# soldering.net
KiCad netlist of a schematic drawn in Altium Designer
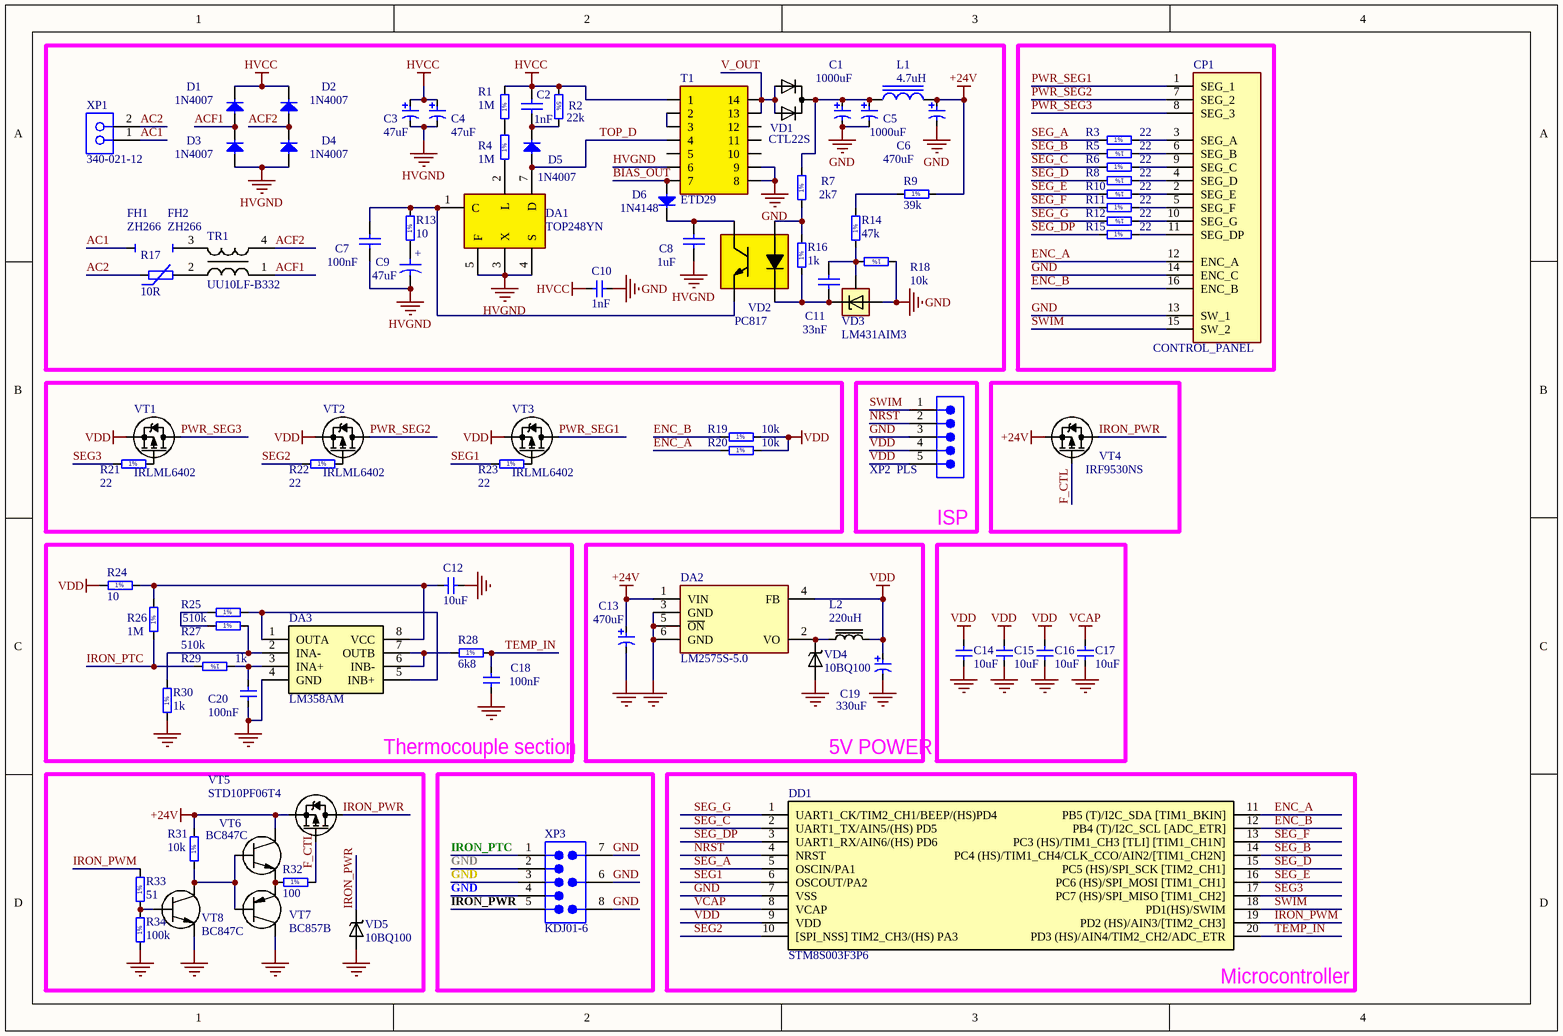
[diagram p0: soldering.SchDoc]

(export (version "E")
  (design (tool "Eeschema 10.0.6"))
  (components
    (comp (ref "C1")
      (value "1000uF")
      (footprint "CAP_EL_13_20_VERT")
      (fields (field (name "PART NUMBER") "SK035M1000B5S-1320 (VERT MOUNTED)") (field (name "VOLTAGE") "35V"))
      (libsource (lib "Capacitor") (part "CAP_POLAR"))
    )
    (comp (ref "C2")
      (value "1nF")
      (footprint "CAPR500-250X720X650")
      (description "Non-polarised capacitor")
      (fields
        (field (name "PART NUMBER") "CPER_1NF_63V_10%_500-250X720X650")
        (field (name "VOLTAGE") "63VDC/40VAC")
        (field (name "AUTHOR") "CERN DEM JLC")
      )
      (libsource (lib "Capacitors") (part "Capacitor - non polarized"))
    )
    (comp (ref "C3")
      (value "47uF")
      (footprint "CAP_EL_16_25_LEFT")
      (fields
        (field (name "PART NUMBER") "SH400M0047B7F-1625 (LEFT MOUNTED)")
        (field (name "VOLTAGE") "400V")
      )
      (libsource (lib "Capacitor") (part "CAP_POLAR"))
    )
    (comp (ref "C4")
      (value "47uF")
      (footprint "CAP_EL_16_25_LEFT")
      (fields
        (field (name "PART NUMBER") "SH400M0047B7F-1625 (LEFT MOUNTED)")
        (field (name "VOLTAGE") "400V")
      )
      (libsource (lib "Capacitor") (part "CAP_POLAR"))
    )
    (comp (ref "C5")
      (value "1000uF")
      (footprint "CAP_EL_13_20_VERT")
      (fields (field (name "PART NUMBER") "SK035M1000B5S-1320 (VERT MOUNTED)") (field (name "VOLTAGE") "35V"))
      (libsource (lib "Capacitor") (part "CAP_POLAR"))
    )
    (comp (ref "C6")
      (value "470uF")
      (footprint "CAP_EL_10_19_VERT")
      (fields (field (name "PART NUMBER") "SJ035M0470B5S-1019 (VERT MOUNTED)") (field (name "VOLTAGE") "35V"))
      (libsource (lib "Capacitor") (part "CAP_POLAR"))
    )
    (comp (ref "C7")
      (value "100nF")
      (footprint "CAPRR508-350X500X500")
      (description "Non-polarised capacitor")
      (fields
        (field (name "PART NUMBER") "CCR_100NF_50V_10%_X7R_508-350X500X500")
        (field (name "VOLTAGE") "50VDC")
        (field (name "AUTHOR") "CERN DEM JLC")
      )
      (libsource (lib "Capacitors") (part "Capacitor - non polarized"))
    )
    (comp (ref "C8")
      (value "1uF")
      (footprint "CAPRR508-508X762X914")
      (description "Non-polarised capacitor")
      (fields
        (field (name "PART NUMBER") "CCR_1UF_50V_10%_X7R_508-508X762X914")
        (field (name "VOLTAGE") "50VDC")
        (field (name "AUTHOR") "CERN DEM JLC")
      )
      (libsource (lib "Capacitors") (part "Capacitor - non polarized"))
    )
    (comp (ref "C9")
      (value "47uF")
      (footprint "CAPPR350-800X1150")
      (description "Polarised capacitor")
      (fields
        (field (name "PART NUMBER") "CAER_47UF_63V_20%_350-800X1150")
        (field (name "VOLTAGE") "63V")
        (field (name "AUTHOR") "CERN DEM JLC")
      )
      (libsource (lib "Capacitors") (part "Capacitor - polarized"))
    )
    (comp (ref "C10")
      (value "1nF")
      (footprint "CAP_7MM_Y")
      (description "SMD 0805 Capacitor")
      (fields (field (name "PART NUMBER") "VKO102KCQTC0KR") (field (name "VOLTAGE") "1000V"))
      (libsource (lib "Capacitor") (part "CAP_NON_POLAR"))
    )
    (comp (ref "C11")
      (value "33nF")
      (footprint "CAPRR254-318X508X660")
      (description "Non-polarised capacitor")
      (fields
        (field (name "PART NUMBER") "CCR_33NF_100V_10%_X7R_254-318X508X660")
        (field (name "VOLTAGE") "100VDC")
        (field (name "AUTHOR") "CERN DEM JLC")
      )
      (libsource (lib "Capacitors") (part "Capacitor - non polarized"))
    )
    (comp (ref "C12")
      (value "10uF")
      (footprint "CAP0805R")
      (description "SMD 0805 Capacitor")
      (fields
        (field (name "PART NUMBER") "CC0805_10UF_10V_10%_X7R")
        (field (name "VOLTAGE") "10V")
        (field (name "AUTHOR") "I. Kuznetsov")
      )
      (libsource (lib "Capacitor") (part "CAP_NON_POLAR"))
    )
    (comp (ref "C13")
      (value "470uF")
      (footprint "CAP_EL_10_19_VERT")
      (fields (field (name "PART NUMBER") "SH050M0470B5S-1019 (VERT MOUNTED)") (field (name "VOLTAGE") "50V"))
      (libsource (lib "Capacitor") (part "CAP_POLAR"))
    )
    (comp (ref "C14")
      (value "10uF")
      (footprint "CAP0805R")
      (description "SMD 0805 Capacitor")
      (fields
        (field (name "PART NUMBER") "CC0805_10UF_10V_10%_X7R")
        (field (name "VOLTAGE") "10V")
        (field (name "AUTHOR") "I. Kuznetsov")
      )
      (libsource (lib "Capacitor") (part "CAP_NON_POLAR"))
    )
    (comp (ref "C15")
      (value "10uF")
      (footprint "CAP0805R")
      (description "SMD 0805 Capacitor")
      (fields
        (field (name "PART NUMBER") "CC0805_10UF_10V_10%_X7R")
        (field (name "VOLTAGE") "10V")
        (field (name "AUTHOR") "I. Kuznetsov")
      )
      (libsource (lib "Capacitor") (part "CAP_NON_POLAR"))
    )
    (comp (ref "C16")
      (value "10uF")
      (footprint "CAP0805R")
      (description "SMD 0805 Capacitor")
      (fields
        (field (name "PART NUMBER") "CC0805_10UF_10V_10%_X7R")
        (field (name "VOLTAGE") "10V")
        (field (name "AUTHOR") "I. Kuznetsov")
      )
      (libsource (lib "Capacitor") (part "CAP_NON_POLAR"))
    )
    (comp (ref "C17")
      (value "10uF")
      (footprint "CAP0805R")
      (description "SMD 0805 Capacitor")
      (fields
        (field (name "PART NUMBER") "CC0805_10UF_10V_10%_X7R")
        (field (name "VOLTAGE") "10V")
        (field (name "AUTHOR") "I. Kuznetsov")
      )
      (libsource (lib "Capacitor") (part "CAP_NON_POLAR"))
    )
    (comp (ref "C18")
      (value "100nF")
      (footprint "CAP0805R")
      (description "SMD 0805 Capacitor")
      (fields
        (field (name "PART NUMBER") "CC0805_100NF_50V_10%_X7R")
        (field (name "VOLTAGE") "50V")
        (field (name "AUTHOR") "I. Kuznetsov")
      )
      (libsource (lib "Capacitor") (part "CAP_NON_POLAR"))
    )
    (comp (ref "C19")
      (value "330uF")
      (footprint "TAN_D")
      (fields (field (name "PART NUMBER") "T495D337M010AHE100") (field (name "VOLTAGE") "10V"))
      (libsource (lib "Capacitor") (part "CAP_POLAR"))
    )
    (comp (ref "C20")
      (value "100nF")
      (footprint "CAP0805R")
      (description "SMD 0805 Capacitor")
      (fields
        (field (name "PART NUMBER") "CC0805_100NF_50V_10%_X7R")
        (field (name "VOLTAGE") "50V")
        (field (name "AUTHOR") "I. Kuznetsov")
      )
      (libsource (lib "Capacitor") (part "CAP_NON_POLAR"))
    )
    (comp (ref "CP1")
      (value "CONTROL_PANEL")
      (footprint "CONTROL_PANEL")
      (libsource (lib "soldering") (part "CONTROL_PANEL"))
    )
    (comp (ref "D1")
      (value "1N4007")
      (footprint "DO-41")
      (description "Diode")
      (fields
        (field (name "VOLTAGE") "1000V")
        (field (name "POWER") "1A")
        (field (name "AUTHOR") "CERN DEM JLC")
      )
      (libsource (lib "ICs And Semiconductors") (part "Diode"))
    )
    (comp (ref "D2")
      (value "1N4007")
      (footprint "DO-41")
      (description "Diode")
      (fields
        (field (name "VOLTAGE") "1000V")
        (field (name "POWER") "1A")
        (field (name "AUTHOR") "CERN DEM JLC")
      )
      (libsource (lib "ICs And Semiconductors") (part "Diode"))
    )
    (comp (ref "D3")
      (value "1N4007")
      (footprint "DO-41")
      (description "Diode")
      (fields
        (field (name "VOLTAGE") "1000V")
        (field (name "POWER") "1A")
        (field (name "AUTHOR") "CERN DEM JLC")
      )
      (libsource (lib "ICs And Semiconductors") (part "Diode"))
    )
    (comp (ref "D4")
      (value "1N4007")
      (footprint "DO-41")
      (description "Diode")
      (fields
        (field (name "VOLTAGE") "1000V")
        (field (name "POWER") "1A")
        (field (name "AUTHOR") "CERN DEM JLC")
      )
      (libsource (lib "ICs And Semiconductors") (part "Diode"))
    )
    (comp (ref "D5")
      (value "1N4007")
      (footprint "DO-41")
      (description "Diode")
      (fields
        (field (name "VOLTAGE") "1000V")
        (field (name "POWER") "1A")
        (field (name "AUTHOR") "CERN DEM JLC")
      )
      (libsource (lib "ICs And Semiconductors") (part "Diode"))
    )
    (comp (ref "D6")
      (value "1N4148")
      (footprint "DO-35")
      (description "Diode")
      (fields
        (field (name "VOLTAGE") "100V")
        (field (name "POWER") "200mA")
        (field (name "AUTHOR") "CERN DEM JLC")
      )
      (libsource (lib "ICs And Semiconductors") (part "Diode"))
    )
    (comp (ref "DA1")
      (value "TOP248YN")
      (footprint "TO-220-7")
      (libsource (lib "IC And Semiconductor") (part "TOP24x"))
    )
    (comp (ref "DA2")
      (value "LM2575S-5.0")
      (footprint "TO-263-5")
      (fields (field (name "MANUFACTURER") "TI") (field (name "AUTHOR") "I. Kuznetsov"))
      (libsource (lib "IC And Semiconductor") (part "LM2575S"))
    )
    (comp (ref "DA3")
      (value "OP Amp")
      (footprint "SOP8")
      (fields (field (name "PARTNUMBER") "LM358AM"))
      (libsource (lib "tonometr") (part "LM358AM"))
    )
    (comp (ref "DD1")
      (value "8 Bit MCU")
      (footprint "TSSOP20")
      (description "8 Bit MCU (STmicroelectronics)")
      (fields (field (name "PARTNUMBER") "STM8S003F3P6"))
      (libsource (lib "soldering") (part "STM8S003F3P6"))
    )
    (comp (ref "FH1") (value "ZH266") (footprint "ZH266") (libsource (lib "Connector") (part "Fuse Clip")))
    (comp (ref "FH2") (value "ZH266") (footprint "ZH266") (libsource (lib "Connector") (part "Fuse Clip")))
    (comp (ref "L1")
      (value "4.7uH")
      (footprint "SL1016")
      (fields (field (name "PART NUMBER") "SL1016-4R7K 4.7"))
      (libsource (lib "Transformer") (part "CORE_IND"))
    )
    (comp (ref "L2")
      (value "220uH")
      (footprint "SDR1005")
      (fields (field (name "PART NUMBER") "SDR1005-221KL"))
      (libsource (lib "Transformer") (part "Core_Inductor"))
    )
    (comp (ref "R1")
      (value "1M")
      (footprint "RES_AXIAL_0_25_8")
      (fields
        (field (name "PART NUMBER") "RMF_1M_1%_0.6W_50PPM_1016-630X250")
        (field (name "POWER") "0.6W")
        (field (name "TOLERANCE") "±1%")
        (field (name "AUTHOR") "CERN DEM JLC")
      )
      (libsource (lib "Resistor") (part "Resistor - 1%"))
    )
    (comp (ref "R2")
      (value "22k")
      (footprint "RESADV508-1670X520")
      (description "Resistor - 5%")
      (fields
        (field (name "PART NUMBER") "RMF_22K_5%_3W_250PPM_508-1670X520_v")
        (field (name "POWER") "3W")
        (field (name "AUTHOR") "CERN DEM JLC")
      )
      (libsource (lib "Resistors") (part "Resistor - 5%"))
    )
    (comp (ref "R3")
      (value "22")
      (footprint "RES0805R")
      (fields
        (field (name "PART NUMBER") "R0805_22R_1%_0.125W_100PPM")
        (field (name "POWER") "0.125W")
        (field (name "TOLERANCE") "±1%")
        (field (name "AUTHOR") "CERN DEM JLC")
      )
      (libsource (lib "Resistor") (part "Resistor - 1%"))
    )
    (comp (ref "R4")
      (value "1M")
      (footprint "RES_AXIAL_0_25_8")
      (fields
        (field (name "PART NUMBER") "RMF_1M_1%_0.6W_50PPM_1016-630X250")
        (field (name "POWER") "0.6W")
        (field (name "TOLERANCE") "±1%")
        (field (name "AUTHOR") "CERN DEM JLC")
      )
      (libsource (lib "Resistor") (part "Resistor - 1%"))
    )
    (comp (ref "R5")
      (value "22")
      (footprint "RES0805R")
      (fields
        (field (name "PART NUMBER") "R0805_22R_1%_0.125W_100PPM")
        (field (name "POWER") "0.125W")
        (field (name "TOLERANCE") "±1%")
        (field (name "AUTHOR") "CERN DEM JLC")
      )
      (libsource (lib "Resistor") (part "Resistor - 1%"))
    )
    (comp (ref "R6")
      (value "22")
      (footprint "RES0805R")
      (fields
        (field (name "PART NUMBER") "R0805_22R_1%_0.125W_100PPM")
        (field (name "POWER") "0.125W")
        (field (name "TOLERANCE") "±1%")
        (field (name "AUTHOR") "CERN DEM JLC")
      )
      (libsource (lib "Resistor") (part "Resistor - 1%"))
    )
    (comp (ref "R7")
      (value "2k7")
      (footprint "RES1016-630X250")
      (description "Resistor - 1%")
      (fields
        (field (name "PART NUMBER") "RMF_2K7_1%_0.6W_50PPM_1016-630X250")
        (field (name "POWER") "0.6W")
        (field (name "AUTHOR") "CERN DEM JLC")
      )
      (libsource (lib "Resistors") (part "Resistor - 1%"))
    )
    (comp (ref "R8")
      (value "22")
      (footprint "RES0805R")
      (fields
        (field (name "PART NUMBER") "R0805_22R_1%_0.125W_100PPM")
        (field (name "POWER") "0.125W")
        (field (name "TOLERANCE") "±1%")
        (field (name "AUTHOR") "CERN DEM JLC")
      )
      (libsource (lib "Resistor") (part "Resistor - 1%"))
    )
    (comp (ref "R9")
      (value "39k")
      (footprint "RES_AXIAL_0_25_8")
      (fields
        (field (name "PART NUMBER") "RMF_39K_1%_0.6W_50PPM_1016-630X250")
        (field (name "POWER") "0.6W")
        (field (name "TOLERANCE") "±1%")
        (field (name "AUTHOR") "CERN DEM JLC")
      )
      (libsource (lib "Resistor") (part "Resistor - 1%"))
    )
    (comp (ref "R10")
      (value "22")
      (footprint "RES0805R")
      (fields
        (field (name "PART NUMBER") "R0805_22R_1%_0.125W_100PPM")
        (field (name "POWER") "0.125W")
        (field (name "TOLERANCE") "±1%")
        (field (name "AUTHOR") "CERN DEM JLC")
      )
      (libsource (lib "Resistor") (part "Resistor - 1%"))
    )
    (comp (ref "R11")
      (value "22")
      (footprint "RES0805R")
      (fields
        (field (name "PART NUMBER") "R0805_22R_1%_0.125W_100PPM")
        (field (name "POWER") "0.125W")
        (field (name "TOLERANCE") "±1%")
        (field (name "AUTHOR") "CERN DEM JLC")
      )
      (libsource (lib "Resistor") (part "Resistor - 1%"))
    )
    (comp (ref "R12")
      (value "22")
      (footprint "RES0805R")
      (fields
        (field (name "PART NUMBER") "R0805_22R_1%_0.125W_100PPM")
        (field (name "POWER") "0.125W")
        (field (name "TOLERANCE") "±1%")
        (field (name "AUTHOR") "CERN DEM JLC")
      )
      (libsource (lib "Resistor") (part "Resistor - 1%"))
    )
    (comp (ref "R13")
      (value "10")
      (footprint "RES_AXIAL_0_25_8")
      (fields
        (field (name "PART NUMBER") "RMF_10R_1%_0.6W_50PPM_1016-630X250")
        (field (name "POWER") "0.6W")
        (field (name "TOLERANCE") "±1%")
        (field (name "AUTHOR") "CERN DEM JLC")
      )
      (libsource (lib "Resistor") (part "Resistor - 1%"))
    )
    (comp (ref "R14")
      (value "47k")
      (footprint "RES_AXIAL_0_25_8")
      (fields
        (field (name "PART NUMBER") "RMF_47K_1%_0.6W_50PPM_1016-630X250")
        (field (name "POWER") "0.6W")
        (field (name "TOLERANCE") "±1%")
        (field (name "AUTHOR") "CERN DEM JLC")
      )
      (libsource (lib "Resistor") (part "Resistor - 1%"))
    )
    (comp (ref "R15")
      (value "22")
      (footprint "RES0805R")
      (fields
        (field (name "PART NUMBER") "R0805_22R_1%_0.125W_100PPM")
        (field (name "POWER") "0.125W")
        (field (name "TOLERANCE") "±1%")
        (field (name "AUTHOR") "CERN DEM JLC")
      )
      (libsource (lib "Resistor") (part "Resistor - 1%"))
    )
    (comp (ref "R16")
      (value "1k")
      (footprint "RES_AXIAL_0_25_8")
      (fields
        (field (name "PART NUMBER") "RMF_1K_1%_0.6W_50PPM_1016-630X250")
        (field (name "POWER") "0.6W")
        (field (name "TOLERANCE") "±1%")
        (field (name "AUTHOR") "CERN DEM JLC")
      )
      (libsource (lib "Resistor") (part "Resistor - 1%"))
    )
    (comp (ref "R17")
      (value "10R")
      (footprint "B57164K")
      (fields (field (name "PART NUMBER") "B57164K"))
      (libsource (lib "Resistor") (part "Resistor - Thermo"))
    )
    (comp (ref "R18")
      (value "10k")
      (footprint "RES_AXIAL_0_25_8")
      (fields
        (field (name "PART NUMBER") "RMF_10K_1%_0.6W_50PPM_1016-630X250")
        (field (name "POWER") "0.6W")
        (field (name "TOLERANCE") "±1%")
        (field (name "AUTHOR") "CERN DEM JLC")
      )
      (libsource (lib "Resistor") (part "Resistor - 1%"))
    )
    (comp (ref "R19")
      (value "10k")
      (footprint "RES0805R")
      (fields
        (field (name "PART NUMBER") "R0805_10K_1%_0.125W_100PPM")
        (field (name "POWER") "0.125W")
        (field (name "TOLERANCE") "±1%")
        (field (name "AUTHOR") "CERN DEM JLC")
      )
      (libsource (lib "Resistor") (part "Resistor - 1%"))
    )
    (comp (ref "R20")
      (value "10k")
      (footprint "RES0805R")
      (fields
        (field (name "PART NUMBER") "R0805_10K_1%_0.125W_100PPM")
        (field (name "POWER") "0.125W")
        (field (name "TOLERANCE") "±1%")
        (field (name "AUTHOR") "CERN DEM JLC")
      )
      (libsource (lib "Resistor") (part "Resistor - 1%"))
    )
    (comp (ref "R21")
      (value "22")
      (footprint "RES0805R")
      (fields
        (field (name "PART NUMBER") "R0805_22R_1%_0.125W_100PPM")
        (field (name "POWER") "0.125W")
        (field (name "TOLERANCE") "±1%")
        (field (name "AUTHOR") "CERN DEM JLC")
      )
      (libsource (lib "Resistor") (part "Resistor - 1%"))
    )
    (comp (ref "R22")
      (value "22")
      (footprint "RES0805R")
      (fields
        (field (name "PART NUMBER") "R0805_22R_1%_0.125W_100PPM")
        (field (name "POWER") "0.125W")
        (field (name "TOLERANCE") "±1%")
        (field (name "AUTHOR") "CERN DEM JLC")
      )
      (libsource (lib "Resistor") (part "Resistor - 1%"))
    )
    (comp (ref "R23")
      (value "22")
      (footprint "RES0805R")
      (fields
        (field (name "PART NUMBER") "R0805_22R_1%_0.125W_100PPM")
        (field (name "POWER") "0.125W")
        (field (name "TOLERANCE") "±1%")
        (field (name "AUTHOR") "CERN DEM JLC")
      )
      (libsource (lib "Resistor") (part "Resistor - 1%"))
    )
    (comp (ref "R24")
      (value "10")
      (footprint "RES0805R")
      (fields
        (field (name "PART NUMBER") "R0805_10R_1%_0.125W_200PPM")
        (field (name "POWER") "0.125W")
        (field (name "TOLERANCE") "±1%")
        (field (name "AUTHOR") "CERN DEM JLC")
      )
      (libsource (lib "Resistor") (part "Resistor - 1%"))
    )
    (comp (ref "R25")
      (value "510k")
      (footprint "RES0805R")
      (fields
        (field (name "PART NUMBER") "R0805_510K_1%_0.125W_100PPM")
        (field (name "POWER") "0.125W")
        (field (name "TOLERANCE") "±1%")
        (field (name "AUTHOR") "CERN DEM JLC")
      )
      (libsource (lib "Resistor") (part "Resistor - 1%"))
    )
    (comp (ref "R26")
      (value "1M")
      (footprint "RES0805R")
      (fields
        (field (name "PART NUMBER") "R0805_1M_1%_0.125W_100PPM")
        (field (name "POWER") "0.125W")
        (field (name "TOLERANCE") "±1%")
        (field (name "AUTHOR") "CERN DEM JLC")
      )
      (libsource (lib "Resistor") (part "Resistor - 1%"))
    )
    (comp (ref "R27")
      (value "510k")
      (footprint "RES0805R")
      (fields
        (field (name "PART NUMBER") "R0805_510K_1%_0.125W_100PPM")
        (field (name "POWER") "0.125W")
        (field (name "TOLERANCE") "±1%")
        (field (name "AUTHOR") "CERN DEM JLC")
      )
      (libsource (lib "Resistor") (part "Resistor - 1%"))
    )
    (comp (ref "R28")
      (value "6k8")
      (footprint "RES0805R")
      (fields
        (field (name "PART NUMBER") "R0805_6K8_1%_0.125W_100PPM")
        (field (name "POWER") "0.125W")
        (field (name "TOLERANCE") "±1%")
        (field (name "AUTHOR") "CERN DEM JLC")
      )
      (libsource (lib "Resistor") (part "Resistor - 1%"))
    )
    (comp (ref "R29")
      (value "1k")
      (footprint "RES0805R")
      (fields
        (field (name "PART NUMBER") "R0805_1K_1%_0.125W_100PPM")
        (field (name "POWER") "0.125W")
        (field (name "TOLERANCE") "±1%")
        (field (name "AUTHOR") "CERN DEM JLC")
      )
      (libsource (lib "Resistor") (part "Resistor - 1%"))
    )
    (comp (ref "R30")
      (value "1k")
      (footprint "RES0805R")
      (fields
        (field (name "PART NUMBER") "R0805_1K_1%_0.125W_100PPM")
        (field (name "POWER") "0.125W")
        (field (name "TOLERANCE") "±1%")
        (field (name "AUTHOR") "CERN DEM JLC")
      )
      (libsource (lib "Resistor") (part "Resistor - 1%"))
    )
    (comp (ref "R31")
      (value "10k")
      (footprint "RES0805R")
      (fields
        (field (name "PART NUMBER") "R0805_10K_1%_0.125W_100PPM")
        (field (name "POWER") "0.125W")
        (field (name "TOLERANCE") "±1%")
        (field (name "AUTHOR") "CERN DEM JLC")
      )
      (libsource (lib "Resistor") (part "Resistor - 1%"))
    )
    (comp (ref "R32")
      (value "100")
      (footprint "RES0805R")
      (fields
        (field (name "PART NUMBER") "R0805_100R_1%_0.125W_100PPM")
        (field (name "POWER") "0.125W")
        (field (name "TOLERANCE") "±1%")
        (field (name "AUTHOR") "CERN DEM JLC")
      )
      (libsource (lib "Resistor") (part "Resistor - 1%"))
    )
    (comp (ref "R33")
      (value "51")
      (footprint "RES0805R")
      (fields
        (field (name "PART NUMBER") "R0805_51R_1%_0.125W_100PPM")
        (field (name "POWER") "0.125W")
        (field (name "TOLERANCE") "±1%")
        (field (name "AUTHOR") "CERN DEM JLC")
      )
      (libsource (lib "Resistor") (part "Resistor - 1%"))
    )
    (comp (ref "R34")
      (value "100k")
      (footprint "RES0805R")
      (fields
        (field (name "PART NUMBER") "R0805_100K_1%_0.125W_100PPM")
        (field (name "POWER") "0.125W")
        (field (name "TOLERANCE") "±1%")
        (field (name "AUTHOR") "CERN DEM JLC")
      )
      (libsource (lib "Resistor") (part "Resistor - 1%"))
    )
    (comp (ref "T1")
      (value "ETD29")
      (footprint "ETD29")
      (libsource (lib "Transformer") (part "Coil_Former_14pin"))
    )
    (comp (ref "TR1")
      (value "22mH")
      (footprint "CG00008A")
      (fields (field (name "PARTNUMBER") "UU10LF-B332") (field (name "PART NUMBER") "CG00008A"))
      (libsource (lib "Transformer") (part "AC_Filter"))
    )
    (comp (ref "VD1")
      (value "CTL22S")
      (footprint "TO-220-3")
      (libsource (lib "IC And Semiconductor") (part "D_2P_TO220"))
    )
    (comp (ref "VD2") (value "PC817") (footprint "DIP4") (libsource (lib "Optoelectronics") (part "xx817")))
    (comp (ref "VD3")
      (value "LM431AIM3")
      (footprint "TO92")
      (libsource (lib "IC And Semiconductor") (part "Z_3P_TO92"))
    )
    (comp (ref "VD4")
      (value "10BQ100")
      (footprint "DO-214AA")
      (fields (field (name "MANUFACTURER") "IR") (field (name "AUTHOR") "I. Kuznetsov"))
      (libsource (lib "IC And Semiconductor") (part "Diode - Schottky"))
    )
    (comp (ref "VD5")
      (value "10BQ100")
      (footprint "DO-214AA")
      (fields (field (name "MANUFACTURER") "IR") (field (name "AUTHOR") "I. Kuznetsov"))
      (libsource (lib "IC And Semiconductor") (part "Diode - Schottky"))
    )
    (comp (ref "VT1")
      (value "IRLML6402")
      (footprint "SOT23")
      (fields (field (name "AUTHOR") "I. Kuznetsov"))
      (libsource (lib "IC And Semiconductor") (part "P_CH_MOSFET"))
    )
    (comp (ref "VT2")
      (value "IRLML6402")
      (footprint "SOT23")
      (fields (field (name "AUTHOR") "I. Kuznetsov"))
      (libsource (lib "IC And Semiconductor") (part "P_CH_MOSFET"))
    )
    (comp (ref "VT3")
      (value "IRLML6402")
      (footprint "SOT23")
      (fields (field (name "AUTHOR") "I. Kuznetsov"))
      (libsource (lib "IC And Semiconductor") (part "P_CH_MOSFET"))
    )
    (comp (ref "VT4")
      (value "IRF9530NS")
      (footprint "D2PAK")
      (libsource (lib "IC And Semiconductor") (part "P_CH_MOSFET"))
    )
    (comp (ref "VT5")
      (value "STD10PF06T4")
      (footprint "DPAK")
      (fields (field (name "AUTHOR") "I. Kuznetsov"))
      (libsource (lib "IC And Semiconductor") (part "P_CH_MOSFET"))
    )
    (comp (ref "VT6")
      (value "BC847C")
      (footprint "SOT23")
      (fields (field (name "AUTHOR") "I. Kuznetsov"))
      (libsource (lib "IC And Semiconductor") (part "NPN_BIPOLAR_SOT23"))
    )
    (comp (ref "VT7")
      (value "BC857B")
      (footprint "SOT23")
      (fields (field (name "AUTHOR") "I. Kuznetsov"))
      (libsource (lib "IC And Semiconductor") (part "PNP_BIPOLAR"))
    )
    (comp (ref "VT8")
      (value "BC847C")
      (footprint "SOT23")
      (fields (field (name "AUTHOR") "I. Kuznetsov"))
      (libsource (lib "IC And Semiconductor") (part "NPN_BIPOLAR_SOT23"))
    )
    (comp (ref "XP1")
      (value "340-021-12")
      (footprint "340-021-12")
      (libsource (lib "Connector") (part "CN_02S_1W"))
    )
    (comp (ref "XP2")
      (value "PLS")
      (footprint "PLS-05")
      (fields (field (name "PART NUMBER") "PLS-05") (field (name "MANUFACTURER") "AUK"))
      (libsource (lib "Connector") (part "CN_05P_1W"))
    )
    (comp (ref "XP3") (value "KDJ01-6") (footprint "KDJ01-6") (libsource (lib "Connector") (part "KDJ01-6")))
  )
  (nets
    (net (code "1") (name "+24V") (class "Default")
      (node (ref "C13") (pin "2") (pinfunction "2_2") (pintype "passive"))
      (node (ref "C6") (pin "2") (pinfunction "2_2") (pintype "passive"))
      (node (ref "DA2") (pin "1") (pinfunction "VIN_1") (pintype "passive"))
      (node (ref "L1") (pin "2") (pinfunction "2_2") (pintype "passive"))
      (node (ref "R31") (pin "2") (pinfunction "2_2") (pintype "passive"))
      (node (ref "R9") (pin "2") (pinfunction "2_2") (pintype "passive"))
      (node (ref "VT4") (pin "2") (pinfunction "S_2") (pintype "passive"))
      (node (ref "VT5") (pin "2") (pinfunction "S_2") (pintype "passive"))
      (node (ref "VT6") (pin "3") (pinfunction "C_3") (pintype "passive"))
    )
    (net (code "2") (name "/AC1") (class "Default")
      (node (ref "FH1") (pin "1") (pinfunction "1_1") (pintype "passive"))
      (node (ref "XP1") (pin "1") (pinfunction "1_1") (pintype "passive"))
    )
    (net (code "3") (name "/AC2") (class "Default")
      (node (ref "R17") (pin "1") (pinfunction "1_1") (pintype "passive"))
      (node (ref "XP1") (pin "2") (pinfunction "2_2") (pintype "passive"))
    )
    (net (code "4") (name "/ACF1") (class "Default")
      (node (ref "D1") (pin "2") (pinfunction "A_2") (pintype "passive"))
      (node (ref "D3") (pin "1") (pinfunction "C_1") (pintype "passive"))
      (node (ref "TR1") (pin "1") (pinfunction "1_1") (pintype "passive"))
    )
    (net (code "5") (name "/ACF2") (class "Default")
      (node (ref "D2") (pin "2") (pinfunction "A_2") (pintype "passive"))
      (node (ref "D4") (pin "1") (pinfunction "C_1") (pintype "passive"))
      (node (ref "TR1") (pin "4") (pinfunction "4_4") (pintype "passive"))
    )
    (net (code "6") (name "/BIAS_OUT") (class "Default")
      (node (ref "D6") (pin "2") (pinfunction "A_2") (pintype "passive"))
      (node (ref "T1") (pin "7") (pinfunction "7_7") (pintype "passive"))
    )
    (net (code "7") (name "/ENC_A") (class "Default")
      (node (ref "CP1") (pin "12") (pinfunction "ENC_A_12") (pintype "passive"))
      (node (ref "DD1") (pin "11") (pinfunction "PB5_(T)/I2C_SDA_[TIM1_BKIN]_11") (pintype "passive"))
      (node (ref "R20") (pin "1") (pinfunction "1_1") (pintype "passive"))
    )
    (net (code "8") (name "/ENC_B") (class "Default")
      (node (ref "CP1") (pin "16") (pinfunction "ENC_B_16") (pintype "passive"))
      (node (ref "DD1") (pin "12") (pinfunction "PB4_(T)/I2C_SCL_[ADC_ETR]_12") (pintype "passive"))
      (node (ref "R19") (pin "1") (pinfunction "1_1") (pintype "passive"))
    )
    (net (code "9") (name "/F_CTL") (class "Default")
      (node (ref "R32") (pin "2") (pinfunction "2_2") (pintype "passive"))
      (node (ref "VT4") (pin "1") (pinfunction "G_1") (pintype "passive"))
      (node (ref "VT5") (pin "1") (pinfunction "G_1") (pintype "passive"))
    )
    (net (code "10") (name "/IRON_PTC") (class "Default")
      (node (ref "R26") (pin "1") (pinfunction "1_1") (pintype "passive"))
      (node (ref "R29") (pin "2") (pinfunction "2_2") (pintype "passive"))
      (node (ref "XP3") (pin "1") (pinfunction "1_1") (pintype "passive"))
    )
    (net (code "11") (name "/IRON_PWM") (class "Default")
      (node (ref "DD1") (pin "19") (pinfunction "PD2_(HS)/AIN3/[TIM2_CH3]_19") (pintype "passive"))
      (node (ref "R33") (pin "2") (pinfunction "2_2") (pintype "passive"))
    )
    (net (code "12") (name "/IRON_PWR") (class "Default")
      (node (ref "VD5") (pin "K") (pinfunction "K_K") (pintype "passive"))
      (node (ref "VT4") (pin "3") (pinfunction "D_3") (pintype "passive"))
      (node (ref "VT5") (pin "3") (pinfunction "D_3") (pintype "passive"))
      (node (ref "XP3") (pin "5") (pinfunction "5_5") (pintype "passive"))
    )
    (net (code "13") (name "/NRST") (class "Default")
      (node (ref "DD1") (pin "4") (pinfunction "NRST_4") (pintype "passive"))
      (node (ref "XP2") (pin "2") (pinfunction "2_2") (pintype "passive"))
    )
    (net (code "14") (name "/PWR_SEG1") (class "Default")
      (node (ref "CP1") (pin "1") (pinfunction "SEG_1_1") (pintype "passive"))
      (node (ref "VT3") (pin "3") (pinfunction "D_3") (pintype "passive"))
    )
    (net (code "15") (name "/PWR_SEG2") (class "Default")
      (node (ref "CP1") (pin "7") (pinfunction "SEG_2_7") (pintype "passive"))
      (node (ref "VT2") (pin "3") (pinfunction "D_3") (pintype "passive"))
    )
    (net (code "16") (name "/PWR_SEG3") (class "Default")
      (node (ref "CP1") (pin "8") (pinfunction "SEG_3_8") (pintype "passive"))
      (node (ref "VT1") (pin "3") (pinfunction "D_3") (pintype "passive"))
    )
    (net (code "17") (name "/SEG1") (class "Default")
      (node (ref "DD1") (pin "6") (pinfunction "OSCOUT/PA2_6") (pintype "passive"))
      (node (ref "R23") (pin "1") (pinfunction "1_1") (pintype "passive"))
    )
    (net (code "18") (name "/SEG2") (class "Default")
      (node (ref "DD1") (pin "10") (pinfunction "[SPI_NSS]_TIM2_CH3/(HS)_PA3_10") (pintype "passive"))
      (node (ref "R22") (pin "1") (pinfunction "1_1") (pintype "passive"))
    )
    (net (code "19") (name "/SEG3") (class "Default")
      (node (ref "DD1") (pin "17") (pinfunction "PC7_(HS)/SPI_MISO_[TIM1_CH2]_17") (pintype "passive"))
      (node (ref "R21") (pin "1") (pinfunction "1_1") (pintype "passive"))
    )
    (net (code "20") (name "/SEG_A") (class "Default")
      (node (ref "DD1") (pin "5") (pinfunction "OSCIN/PA1_5") (pintype "passive"))
      (node (ref "R3") (pin "1") (pinfunction "1_1") (pintype "passive"))
    )
    (net (code "21") (name "/SEG_B") (class "Default")
      (node (ref "DD1") (pin "14") (pinfunction "PC4_(HS)/TIM1_CH4/CLK_CCO/AIN2/[TIM1_CH2N]_14") (pintype "passive"))
      (node (ref "R5") (pin "2") (pinfunction "2_2") (pintype "passive"))
    )
    (net (code "22") (name "/SEG_C") (class "Default")
      (node (ref "DD1") (pin "2") (pinfunction "UART1_TX/AIN5/(HS)_PD5_2") (pintype "passive"))
      (node (ref "R6") (pin "1") (pinfunction "1_1") (pintype "passive"))
    )
    (net (code "23") (name "/SEG_D") (class "Default")
      (node (ref "DD1") (pin "15") (pinfunction "PC5_(HS)/SPI_SCK_[TIM2_CH1]_15") (pintype "passive"))
      (node (ref "R8") (pin "2") (pinfunction "2_2") (pintype "passive"))
    )
    (net (code "24") (name "/SEG_DP") (class "Default")
      (node (ref "DD1") (pin "3") (pinfunction "UART1_RX/AIN6/(HS)_PD6_3") (pintype "passive"))
      (node (ref "R15") (pin "1") (pinfunction "1_1") (pintype "passive"))
    )
    (net (code "25") (name "/SEG_E") (class "Default")
      (node (ref "DD1") (pin "16") (pinfunction "PC6_(HS)/SPI_MOSI_[TIM1_CH1]_16") (pintype "passive"))
      (node (ref "R10") (pin "2") (pinfunction "2_2") (pintype "passive"))
    )
    (net (code "26") (name "/SEG_F") (class "Default")
      (node (ref "DD1") (pin "13") (pinfunction "PC3_(HS)/TIM1_CH3_[TLI]_[TIM1_CH1N]_13") (pintype "passive"))
      (node (ref "R11") (pin "1") (pinfunction "1_1") (pintype "passive"))
    )
    (net (code "27") (name "/SEG_G") (class "Default")
      (node (ref "DD1") (pin "1") (pinfunction "UART1_CK/TIM2_CH1/BEEP/(HS)PD4_1") (pintype "passive"))
      (node (ref "R12") (pin "2") (pinfunction "2_2") (pintype "passive"))
    )
    (net (code "28") (name "/SWIM") (class "Default")
      (node (ref "CP1") (pin "15") (pinfunction "SW_2_15") (pintype "passive"))
      (node (ref "DD1") (pin "18") (pinfunction "PD1(HS)/SWIM_18") (pintype "passive"))
      (node (ref "XP2") (pin "1") (pinfunction "1_1") (pintype "passive"))
    )
    (net (code "29") (name "/TEMP_IN") (class "Default")
      (node (ref "C18") (pin "2") (pinfunction "2_2") (pintype "passive"))
      (node (ref "DD1") (pin "20") (pinfunction "PD3_(HS)/AIN4/TIM2_CH2/ADC_ETR_20") (pintype "passive"))
      (node (ref "R28") (pin "2") (pinfunction "2_2") (pintype "passive"))
    )
    (net (code "30") (name "/TOP_D") (class "Default")
      (node (ref "D5") (pin "2") (pinfunction "A_2") (pintype "passive"))
      (node (ref "DA1") (pin "7") (pinfunction "D_7") (pintype "passive"))
      (node (ref "T1") (pin "4") (pinfunction "4_4") (pintype "passive"))
    )
    (net (code "31") (name "/V_OUT") (class "Default")
      (node (ref "T1") (pin "13") (pinfunction "13_13") (pintype "passive"))
      (node (ref "T1") (pin "14") (pinfunction "14_14") (pintype "passive"))
      (node (ref "VD1") (pin "1") (pinfunction "A_1") (pintype "passive"))
      (node (ref "VD1") (pin "3") (pinfunction "A_3") (pintype "passive"))
    )
    (net (code "32") (name "GND") (class "Default")
      (node (ref "C1") (pin "1") (pinfunction "1_1") (pintype "passive"))
      (node (ref "C10") (pin "2") (pinfunction "2_2") (pintype "passive"))
      (node (ref "C12") (pin "2") (pinfunction "2_2") (pintype "passive"))
      (node (ref "C13") (pin "1") (pinfunction "1_1") (pintype "passive"))
      (node (ref "C14") (pin "1") (pinfunction "1_1") (pintype "passive"))
      (node (ref "C15") (pin "1") (pinfunction "1_1") (pintype "passive"))
      (node (ref "C16") (pin "1") (pinfunction "1_1") (pintype "passive"))
      (node (ref "C17") (pin "1") (pinfunction "1_1") (pintype "passive"))
      (node (ref "C18") (pin "1") (pinfunction "1_1") (pintype "passive"))
      (node (ref "C19") (pin "1") (pinfunction "1_1") (pintype "passive"))
      (node (ref "C20") (pin "1") (pinfunction "1_1") (pintype "passive"))
      (node (ref "C5") (pin "1") (pinfunction "1_1") (pintype "passive"))
      (node (ref "C6") (pin "1") (pinfunction "1_1") (pintype "passive"))
      (node (ref "CP1") (pin "13") (pinfunction "SW_1_13") (pintype "passive"))
      (node (ref "CP1") (pin "14") (pinfunction "ENC_C_14") (pintype "passive"))
      (node (ref "DA2") (pin "3") (pinfunction "GND_3") (pintype "passive"))
      (node (ref "DA2") (pin "5") (pinfunction "~{ON}_5") (pintype "passive"))
      (node (ref "DA2") (pin "6") (pinfunction "GND_6") (pintype "passive"))
      (node (ref "DA3") (pin "4") (pinfunction "GND_4") (pintype "passive"))
      (node (ref "DD1") (pin "7") (pinfunction "VSS_7") (pintype "passive"))
      (node (ref "R18") (pin "1") (pinfunction "1_1") (pintype "passive"))
      (node (ref "R30") (pin "1") (pinfunction "1_1") (pintype "passive"))
      (node (ref "R34") (pin "1") (pinfunction "1_1") (pintype "passive"))
      (node (ref "T1") (pin "8") (pinfunction "8_8") (pintype "passive"))
      (node (ref "T1") (pin "9") (pinfunction "9_9") (pintype "passive"))
      (node (ref "VD3") (pin "2") (pinfunction "A_2") (pintype "passive"))
      (node (ref "VD4") (pin "A") (pinfunction "A_A") (pintype "passive"))
      (node (ref "VD5") (pin "A") (pinfunction "A_A") (pintype "passive"))
      (node (ref "VT7") (pin "3") (pinfunction "C_3") (pintype "passive"))
      (node (ref "VT8") (pin "2") (pinfunction "E_2") (pintype "passive"))
      (node (ref "XP2") (pin "3") (pinfunction "3_3") (pintype "passive"))
      (node (ref "XP3") (pin "2") (pinfunction "2_2") (pintype "passive"))
      (node (ref "XP3") (pin "3") (pinfunction "3_3") (pintype "passive"))
      (node (ref "XP3") (pin "4") (pinfunction "4_4") (pintype "passive"))
      (node (ref "XP3") (pin "6") (pinfunction "6_6") (pintype "passive"))
      (node (ref "XP3") (pin "7") (pinfunction "7_7") (pintype "passive"))
      (node (ref "XP3") (pin "8") (pinfunction "8_8") (pintype "passive"))
    )
    (net (code "33") (name "HVCC") (class "Default")
      (node (ref "C10") (pin "1") (pinfunction "1_1") (pintype "passive"))
      (node (ref "C2") (pin "2") (pinfunction "2_2") (pintype "passive"))
      (node (ref "C3") (pin "2") (pinfunction "2_2") (pintype "passive"))
      (node (ref "C4") (pin "2") (pinfunction "2_2") (pintype "passive"))
      (node (ref "D1") (pin "1") (pinfunction "C_1") (pintype "passive"))
      (node (ref "D2") (pin "1") (pinfunction "C_1") (pintype "passive"))
      (node (ref "R1") (pin "2") (pinfunction "2_2") (pintype "passive"))
      (node (ref "R2") (pin "1") (pinfunction "1_1") (pintype "passive"))
      (node (ref "T1") (pin "1") (pinfunction "1_1") (pintype "passive"))
    )
    (net (code "34") (name "HVGND") (class "Default")
      (node (ref "C3") (pin "1") (pinfunction "1_1") (pintype "passive"))
      (node (ref "C4") (pin "1") (pinfunction "1_1") (pintype "passive"))
      (node (ref "C7") (pin "2") (pinfunction "2_2") (pintype "passive"))
      (node (ref "C8") (pin "1") (pinfunction "1_1") (pintype "passive"))
      (node (ref "C9") (pin "2") (pinfunction "2_2") (pintype "passive"))
      (node (ref "D3") (pin "2") (pinfunction "A_2") (pintype "passive"))
      (node (ref "D4") (pin "2") (pinfunction "A_2") (pintype "passive"))
      (node (ref "DA1") (pin "3") (pinfunction "X_3") (pintype "passive"))
      (node (ref "DA1") (pin "4") (pinfunction "S_4") (pintype "passive"))
      (node (ref "DA1") (pin "5") (pinfunction "F_5") (pintype "passive"))
      (node (ref "T1") (pin "6") (pinfunction "6_6") (pintype "passive"))
    )
    (net (code "35") (name "Net-(C9-Pad1)") (class "Default")
      (node (ref "C9") (pin "1") (pinfunction "1_1") (pintype "passive"))
      (node (ref "R13") (pin "1") (pinfunction "1_1") (pintype "passive"))
    )
    (net (code "36") (name "Net-(CP1-SEG_A)") (class "Default")
      (node (ref "CP1") (pin "3") (pinfunction "SEG_A_3") (pintype "passive"))
      (node (ref "R3") (pin "2") (pinfunction "2_2") (pintype "passive"))
    )
    (net (code "37") (name "Net-(CP1-SEG_B)") (class "Default")
      (node (ref "CP1") (pin "6") (pinfunction "SEG_B_6") (pintype "passive"))
      (node (ref "R5") (pin "1") (pinfunction "1_1") (pintype "passive"))
    )
    (net (code "38") (name "Net-(CP1-SEG_C)") (class "Default")
      (node (ref "CP1") (pin "9") (pinfunction "SEG_C_9") (pintype "passive"))
      (node (ref "R6") (pin "2") (pinfunction "2_2") (pintype "passive"))
    )
    (net (code "39") (name "Net-(CP1-SEG_D)") (class "Default")
      (node (ref "CP1") (pin "4") (pinfunction "SEG_D_4") (pintype "passive"))
      (node (ref "R8") (pin "1") (pinfunction "1_1") (pintype "passive"))
    )
    (net (code "40") (name "Net-(CP1-SEG_DP)") (class "Default")
      (node (ref "CP1") (pin "11") (pinfunction "SEG_DP_11") (pintype "passive"))
      (node (ref "R15") (pin "2") (pinfunction "2_2") (pintype "passive"))
    )
    (net (code "41") (name "Net-(CP1-SEG_E)") (class "Default")
      (node (ref "CP1") (pin "2") (pinfunction "SEG_E_2") (pintype "passive"))
      (node (ref "R10") (pin "1") (pinfunction "1_1") (pintype "passive"))
    )
    (net (code "42") (name "Net-(CP1-SEG_F)") (class "Default")
      (node (ref "CP1") (pin "5") (pinfunction "SEG_F_5") (pintype "passive"))
      (node (ref "R11") (pin "2") (pinfunction "2_2") (pintype "passive"))
    )
    (net (code "43") (name "Net-(CP1-SEG_G)") (class "Default")
      (node (ref "CP1") (pin "10") (pinfunction "SEG_G_10") (pintype "passive"))
      (node (ref "R12") (pin "1") (pinfunction "1_1") (pintype "passive"))
    )
    (net (code "44") (name "Net-(D5-C)") (class "Default")
      (node (ref "C2") (pin "1") (pinfunction "1_1") (pintype "passive"))
      (node (ref "D5") (pin "1") (pinfunction "C_1") (pintype "passive"))
      (node (ref "R2") (pin "2") (pinfunction "2_2") (pintype "passive"))
    )
    (net (code "45") (name "Net-(D6-C)") (class "Default")
      (node (ref "C8") (pin "2") (pinfunction "2_2") (pintype "passive"))
      (node (ref "D6") (pin "1") (pinfunction "C_1") (pintype "passive"))
      (node (ref "VD2") (pin "4") (pinfunction "C_4") (pintype "passive"))
    )
    (net (code "46") (name "Net-(DA1-C)") (class "Default")
      (node (ref "C7") (pin "1") (pinfunction "1_1") (pintype "passive"))
      (node (ref "DA1") (pin "1") (pinfunction "C_1") (pintype "passive"))
      (node (ref "R13") (pin "2") (pinfunction "2_2") (pintype "passive"))
      (node (ref "VD2") (pin "3") (pinfunction "E_3") (pintype "passive"))
    )
    (net (code "47") (name "Net-(DA1-L)") (class "Default")
      (node (ref "DA1") (pin "2") (pinfunction "L_2") (pintype "passive"))
      (node (ref "R4") (pin "1") (pinfunction "1_1") (pintype "passive"))
    )
    (net (code "48") (name "Net-(DA2-VO)") (class "Default")
      (node (ref "DA2") (pin "2") (pinfunction "VO_2") (pintype "passive"))
      (node (ref "L2") (pin "1") (pinfunction "1_1") (pintype "passive"))
      (node (ref "VD4") (pin "K") (pinfunction "K_K") (pintype "passive"))
    )
    (net (code "49") (name "Net-(DA3-INA+)") (class "Default")
      (node (ref "C20") (pin "2") (pinfunction "2_2") (pintype "passive"))
      (node (ref "DA3") (pin "3") (pinfunction "INA+_3") (pintype "passive"))
      (node (ref "R29") (pin "1") (pinfunction "1_1") (pintype "passive"))
    )
    (net (code "50") (name "Net-(DA3-INA-)") (class "Default")
      (node (ref "DA3") (pin "2") (pinfunction "INA-_2") (pintype "passive"))
      (node (ref "R27") (pin "2") (pinfunction "2_2") (pintype "passive"))
      (node (ref "R30") (pin "2") (pinfunction "2_2") (pintype "passive"))
    )
    (net (code "51") (name "Net-(DA3-INB+)") (class "Default")
      (node (ref "DA3") (pin "1") (pinfunction "OUTA_1") (pintype "passive"))
      (node (ref "DA3") (pin "5") (pinfunction "INB+_5") (pintype "passive"))
      (node (ref "R25") (pin "2") (pinfunction "2_2") (pintype "passive"))
    )
    (net (code "52") (name "Net-(DA3-INB-)") (class "Default")
      (node (ref "DA3") (pin "6") (pinfunction "INB-_6") (pintype "passive"))
      (node (ref "DA3") (pin "7") (pinfunction "OUTB_7") (pintype "passive"))
      (node (ref "R28") (pin "1") (pinfunction "1_1") (pintype "passive"))
    )
    (net (code "53") (name "Net-(DA3-VCC)") (class "Default")
      (node (ref "C12") (pin "1") (pinfunction "1_1") (pintype "passive"))
      (node (ref "DA3") (pin "8") (pinfunction "VCC_8") (pintype "passive"))
      (node (ref "R24") (pin "2") (pinfunction "2_2") (pintype "passive"))
      (node (ref "R26") (pin "2") (pinfunction "2_2") (pintype "passive"))
    )
    (net (code "54") (name "Net-(FH2-Pad1)") (class "Default")
      (node (ref "FH2") (pin "1") (pinfunction "1_1") (pintype "passive"))
      (node (ref "TR1") (pin "3") (pinfunction "3_3") (pintype "passive"))
    )
    (net (code "55") (name "Net-(R1-Pad1)") (class "Default")
      (node (ref "R1") (pin "1") (pinfunction "1_1") (pintype "passive"))
      (node (ref "R4") (pin "2") (pinfunction "2_2") (pintype "passive"))
    )
    (net (code "56") (name "Net-(R14-Pad2)") (class "Default")
      (node (ref "R14") (pin "2") (pinfunction "2_2") (pintype "passive"))
      (node (ref "R9") (pin "1") (pinfunction "1_1") (pintype "passive"))
    )
    (net (code "57") (name "Net-(R17-Pad2)") (class "Default")
      (node (ref "R17") (pin "2") (pinfunction "2_2") (pintype "passive"))
      (node (ref "TR1") (pin "2") (pinfunction "2_2") (pintype "passive"))
    )
    (net (code "58") (name "Net-(R25-Pad1)") (class "Default")
      (node (ref "R25") (pin "1") (pinfunction "1_1") (pintype "passive"))
      (node (ref "R27") (pin "1") (pinfunction "1_1") (pintype "passive"))
    )
    (net (code "59") (name "Net-(T1-Pad2)") (class "Default")
      (node (ref "T1") (pin "2") (pinfunction "2_2") (pintype "passive"))
      (node (ref "T1") (pin "3") (pinfunction "3_3") (pintype "passive"))
    )
    (net (code "60") (name "Net-(VD1-K)") (class "Default")
      (node (ref "C1") (pin "2") (pinfunction "2_2") (pintype "passive"))
      (node (ref "C5") (pin "2") (pinfunction "2_2") (pintype "passive"))
      (node (ref "L1") (pin "1") (pinfunction "1_1") (pintype "passive"))
      (node (ref "R7") (pin "2") (pinfunction "2_2") (pintype "passive"))
      (node (ref "VD1") (pin "2") (pinfunction "K_2") (pintype "passive"))
    )
    (net (code "61") (name "Net-(VD2-A)") (class "Default")
      (node (ref "R16") (pin "2") (pinfunction "2_2") (pintype "passive"))
      (node (ref "R7") (pin "1") (pinfunction "1_1") (pintype "passive"))
      (node (ref "VD2") (pin "1") (pinfunction "A_1") (pintype "passive"))
    )
    (net (code "62") (name "Net-(VD2-K)") (class "Default")
      (node (ref "C11") (pin "2") (pinfunction "2_2") (pintype "passive"))
      (node (ref "R16") (pin "1") (pinfunction "1_1") (pintype "passive"))
      (node (ref "VD2") (pin "2") (pinfunction "K_2") (pintype "passive"))
      (node (ref "VD3") (pin "1") (pinfunction "K_1") (pintype "passive"))
    )
    (net (code "63") (name "Net-(VD3-REF)") (class "Default")
      (node (ref "C11") (pin "1") (pinfunction "1_1") (pintype "passive"))
      (node (ref "R14") (pin "1") (pinfunction "1_1") (pintype "passive"))
      (node (ref "R18") (pin "2") (pinfunction "2_2") (pintype "passive"))
      (node (ref "VD3") (pin "3") (pinfunction "REF_3") (pintype "passive"))
    )
    (net (code "64") (name "Net-(VT1-G)") (class "Default")
      (node (ref "R21") (pin "2") (pinfunction "2_2") (pintype "passive"))
      (node (ref "VT1") (pin "1") (pinfunction "G_1") (pintype "passive"))
    )
    (net (code "65") (name "Net-(VT2-G)") (class "Default")
      (node (ref "R22") (pin "2") (pinfunction "2_2") (pintype "passive"))
      (node (ref "VT2") (pin "1") (pinfunction "G_1") (pintype "passive"))
    )
    (net (code "66") (name "Net-(VT3-G)") (class "Default")
      (node (ref "R23") (pin "2") (pinfunction "2_2") (pintype "passive"))
      (node (ref "VT3") (pin "1") (pinfunction "G_1") (pintype "passive"))
    )
    (net (code "67") (name "Net-(VT6-B)") (class "Default")
      (node (ref "R31") (pin "1") (pinfunction "1_1") (pintype "passive"))
      (node (ref "VT6") (pin "1") (pinfunction "B_1") (pintype "passive"))
      (node (ref "VT7") (pin "1") (pinfunction "B_1") (pintype "passive"))
      (node (ref "VT8") (pin "3") (pinfunction "C_3") (pintype "passive"))
    )
    (net (code "68") (name "Net-(VT6-E)") (class "Default")
      (node (ref "R32") (pin "1") (pinfunction "1_1") (pintype "passive"))
      (node (ref "VT6") (pin "2") (pinfunction "E_2") (pintype "passive"))
      (node (ref "VT7") (pin "2") (pinfunction "E_2") (pintype "passive"))
    )
    (net (code "69") (name "Net-(VT8-B)") (class "Default")
      (node (ref "R33") (pin "1") (pinfunction "1_1") (pintype "passive"))
      (node (ref "R34") (pin "2") (pinfunction "2_2") (pintype "passive"))
      (node (ref "VT8") (pin "1") (pinfunction "B_1") (pintype "passive"))
    )
    (net (code "70") (name "VCAP") (class "Default")
      (node (ref "C17") (pin "2") (pinfunction "2_2") (pintype "passive"))
      (node (ref "DD1") (pin "8") (pinfunction "VCAP_8") (pintype "passive"))
    )
    (net (code "71") (name "VDD") (class "Default")
      (node (ref "C14") (pin "2") (pinfunction "2_2") (pintype "passive"))
      (node (ref "C15") (pin "2") (pinfunction "2_2") (pintype "passive"))
      (node (ref "C16") (pin "2") (pinfunction "2_2") (pintype "passive"))
      (node (ref "C19") (pin "2") (pinfunction "2_2") (pintype "passive"))
      (node (ref "DA2") (pin "4") (pinfunction "FB_4") (pintype "passive"))
      (node (ref "DD1") (pin "9") (pinfunction "VDD_9") (pintype "passive"))
      (node (ref "L2") (pin "2") (pinfunction "2_2") (pintype "passive"))
      (node (ref "R19") (pin "2") (pinfunction "2_2") (pintype "passive"))
      (node (ref "R20") (pin "2") (pinfunction "2_2") (pintype "passive"))
      (node (ref "R24") (pin "1") (pinfunction "1_1") (pintype "passive"))
      (node (ref "VT1") (pin "2") (pinfunction "S_2") (pintype "passive"))
      (node (ref "VT2") (pin "2") (pinfunction "S_2") (pintype "passive"))
      (node (ref "VT3") (pin "2") (pinfunction "S_2") (pintype "passive"))
      (node (ref "XP2") (pin "4") (pinfunction "4_4") (pintype "passive"))
      (node (ref "XP2") (pin "5") (pinfunction "5_5") (pintype "passive"))
    )
    (net (code "72") (name "unconnected-(T1-Pad5)") (class "Default")
      (node (ref "T1") (pin "5") (pinfunction "5_5") (pintype "passive"))
    )
    (net (code "73") (name "unconnected-(T1-Pad10)") (class "Default")
      (node (ref "T1") (pin "10") (pinfunction "10_10") (pintype "passive"))
    )
    (net (code "74") (name "unconnected-(T1-Pad11)") (class "Default")
      (node (ref "T1") (pin "11") (pinfunction "11_11") (pintype "passive"))
    )
    (net (code "75") (name "unconnected-(T1-Pad12)") (class "Default")
      (node (ref "T1") (pin "12") (pinfunction "12_12") (pintype "passive"))
    )
  )
)
